# platine.net
KiCad netlist of a schematic drawn in EAGLE
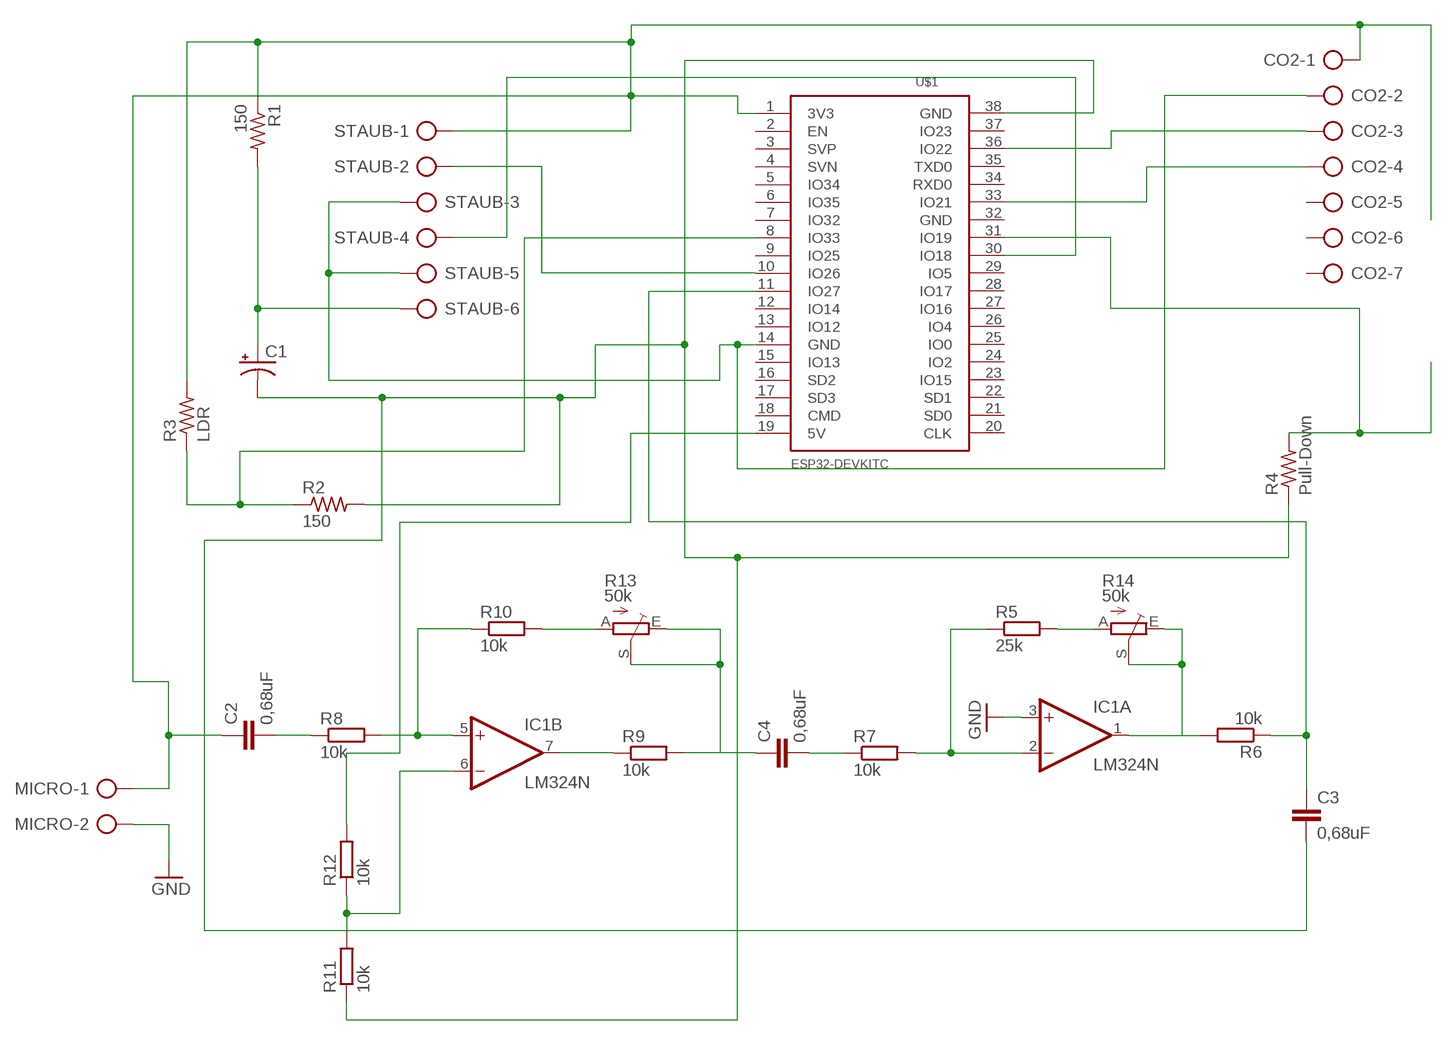
[diagram p0: schematic, sheet 1]

(export (version "E")
  (design (tool "Eeschema 10.0.6"))
  (components
    (comp (ref "C1")
      (value "CPOL-USE2,5-6E")
      (footprint "eagle-import:E2,5-6E")
      (libsource (lib "eagle-import") (part "CPOL-USE2,5-6E"))
    )
    (comp (ref "C2")
      (value "0,68uF")
      (footprint "eagle-import:C025-025X050")
      (libsource (lib "eagle-import") (part "C-EU025-025X050"))
    )
    (comp (ref "C3")
      (value "0,68uF")
      (footprint "eagle-import:C025-025X050")
      (libsource (lib "eagle-import") (part "C-EU025-025X050"))
    )
    (comp (ref "C4")
      (value "0,68uF")
      (footprint "eagle-import:C025-025X050")
      (libsource (lib "eagle-import") (part "C-EU025-025X050"))
    )
    (comp (ref "CO2")
      (value "AK300/7")
      (footprint "eagle-import:AK300_7")
      (libsource (lib "eagle-import") (part "AK300/7"))
    )
    (comp (ref "IC1")
      (value "LM324N")
      (footprint "eagle-import:DIL14")
      (libsource (lib "eagle-import") (part "LM324N"))
    )
    (comp (ref "MICRO")
      (value "AK300/2")
      (footprint "eagle-import:AK300_2")
      (libsource (lib "eagle-import") (part "AK300/2"))
    )
    (comp (ref "R1")
      (value "150")
      (footprint "eagle-import:0207_10")
      (libsource (lib "eagle-import") (part "R-US_0207/10"))
    )
    (comp (ref "R2")
      (value "150")
      (footprint "eagle-import:0207_10")
      (libsource (lib "eagle-import") (part "R-US_0207/10"))
    )
    (comp (ref "R3")
      (value "LDR")
      (footprint "eagle-import:V234_12")
      (libsource (lib "eagle-import") (part "R-US_V234/12"))
    )
    (comp (ref "R4")
      (value "Pull-Down")
      (footprint "eagle-import:0207_10")
      (libsource (lib "eagle-import") (part "R-US_0207/10"))
    )
    (comp (ref "R5")
      (value "25k")
      (footprint "eagle-import:0204_7")
      (libsource (lib "eagle-import") (part "R-EU_0204/7"))
    )
    (comp (ref "R6")
      (value "10k")
      (footprint "eagle-import:0204_7")
      (libsource (lib "eagle-import") (part "R-EU_0204/7"))
    )
    (comp (ref "R7")
      (value "10k")
      (footprint "eagle-import:0204_7")
      (libsource (lib "eagle-import") (part "R-EU_0204/7"))
    )
    (comp (ref "R8")
      (value "10k")
      (footprint "eagle-import:0204_7")
      (libsource (lib "eagle-import") (part "R-EU_0204/7"))
    )
    (comp (ref "R9")
      (value "10k")
      (footprint "eagle-import:0204_7")
      (libsource (lib "eagle-import") (part "R-EU_0204/7"))
    )
    (comp (ref "R10")
      (value "10k")
      (footprint "eagle-import:0204_7")
      (libsource (lib "eagle-import") (part "R-EU_0204/7"))
    )
    (comp (ref "R11")
      (value "10k")
      (footprint "eagle-import:0204_7")
      (libsource (lib "eagle-import") (part "R-EU_0204/7"))
    )
    (comp (ref "R12")
      (value "10k")
      (footprint "eagle-import:0204_7")
      (libsource (lib "eagle-import") (part "R-EU_0204/7"))
    )
    (comp (ref "R13")
      (value "50k")
      (footprint "eagle-import:LI10")
      (libsource (lib "eagle-import") (part "TRIM_EU-LI10"))
    )
    (comp (ref "R14")
      (value "50k")
      (footprint "eagle-import:LI10")
      (libsource (lib "eagle-import") (part "TRIM_EU-LI10"))
    )
    (comp (ref "STAUB")
      (value "AK300/6")
      (footprint "eagle-import:AK300_6")
      (libsource (lib "eagle-import") (part "AK300/6"))
    )
    (comp (ref "U$1")
      (value "ESP32DEVKITC")
      (footprint "eagle-import:ESP32-DEVKITC")
      (libsource (lib "eagle-import") (part "ESP32DEVKITC"))
    )
  )
  (nets
    (net (code "1") (name "GND") (class "Default")
      (node (ref "IC1") (pin "3") (pinfunction "+IN_3") (pintype "input"))
      (node (ref "MICRO") (pin "2") (pinfunction "KL_2") (pintype "passive"))
    )
    (net (code "2") (name "Net-(C1-Pad-)") (class "Default")
      (node (ref "C1") (pin "-") (pinfunction "-_-") (pintype "passive"))
      (node (ref "C3") (pin "2") (pinfunction "2_2") (pintype "passive"))
      (node (ref "R11") (pin "1") (pinfunction "1_1") (pintype "passive"))
      (node (ref "R2") (pin "2") (pinfunction "2_2") (pintype "passive"))
      (node (ref "R4") (pin "1") (pinfunction "1_1") (pintype "passive"))
      (node (ref "U$1") (pin "38") (pinfunction "GND_38") (pintype "bidirectional"))
    )
    (net (code "3") (name "Net-(C2-Pad2)") (class "Default")
      (node (ref "C2") (pin "2") (pinfunction "2_2") (pintype "passive"))
      (node (ref "R8") (pin "1") (pinfunction "1_1") (pintype "passive"))
    )
    (net (code "4") (name "Net-(C4-Pad1)") (class "Default")
      (node (ref "C4") (pin "1") (pinfunction "1_1") (pintype "passive"))
      (node (ref "R13") (pin "E") (pinfunction "E_E") (pintype "passive"))
      (node (ref "R13") (pin "S") (pinfunction "S_S") (pintype "passive"))
      (node (ref "R9") (pin "2") (pinfunction "2_2") (pintype "passive"))
    )
    (net (code "5") (name "Net-(C4-Pad2)") (class "Default")
      (node (ref "C4") (pin "2") (pinfunction "2_2") (pintype "passive"))
      (node (ref "R7") (pin "1") (pinfunction "1_1") (pintype "passive"))
    )
    (net (code "6") (name "Net-(CO2A-KL)") (class "Default")
      (node (ref "C2") (pin "1") (pinfunction "1_1") (pintype "passive"))
      (node (ref "CO2") (pin "1") (pinfunction "KL_1") (pintype "passive"))
      (node (ref "MICRO") (pin "1") (pinfunction "KL_1") (pintype "passive"))
      (node (ref "R1") (pin "1") (pinfunction "1_1") (pintype "passive"))
      (node (ref "R3") (pin "2") (pinfunction "2_2") (pintype "passive"))
      (node (ref "STAUB") (pin "1") (pinfunction "KL_1") (pintype "passive"))
      (node (ref "U$1") (pin "1") (pinfunction "3V3_1") (pintype "bidirectional"))
    )
    (net (code "7") (name "Net-(CO2B-KL)") (class "Default")
      (node (ref "CO2") (pin "2") (pinfunction "KL_2") (pintype "passive"))
      (node (ref "STAUB") (pin "3") (pinfunction "KL_3") (pintype "passive"))
      (node (ref "STAUB") (pin "5") (pinfunction "KL_5") (pintype "passive"))
      (node (ref "U$1") (pin "14") (pinfunction "GND_14") (pintype "bidirectional"))
    )
    (net (code "8") (name "Net-(CO2C-KL)") (class "Default")
      (node (ref "CO2") (pin "3") (pinfunction "KL_3") (pintype "passive"))
      (node (ref "U$1") (pin "36") (pinfunction "IO22_36") (pintype "bidirectional"))
    )
    (net (code "9") (name "Net-(CO2D-KL)") (class "Default")
      (node (ref "CO2") (pin "4") (pinfunction "KL_4") (pintype "passive"))
      (node (ref "U$1") (pin "33") (pinfunction "IO21_33") (pintype "bidirectional"))
    )
    (net (code "10") (name "Net-(IC1A--IN)") (class "Default")
      (node (ref "IC1") (pin "2") (pinfunction "-IN_2") (pintype "input"))
      (node (ref "R5") (pin "1") (pinfunction "1_1") (pintype "passive"))
      (node (ref "R7") (pin "2") (pinfunction "2_2") (pintype "passive"))
    )
    (net (code "11") (name "Net-(IC1A-OUT)") (class "Default")
      (node (ref "IC1") (pin "1") (pinfunction "OUT_1") (pintype "output"))
      (node (ref "R14") (pin "E") (pinfunction "E_E") (pintype "passive"))
      (node (ref "R14") (pin "S") (pinfunction "S_S") (pintype "passive"))
      (node (ref "R6") (pin "2") (pinfunction "2_2") (pintype "passive"))
    )
    (net (code "12") (name "Net-(IC1B-+IN)") (class "Default")
      (node (ref "IC1") (pin "5") (pinfunction "+IN_5") (pintype "input"))
      (node (ref "R10") (pin "1") (pinfunction "1_1") (pintype "passive"))
      (node (ref "R8") (pin "2") (pinfunction "2_2") (pintype "passive"))
    )
    (net (code "13") (name "Net-(IC1B--IN)") (class "Default")
      (node (ref "IC1") (pin "6") (pinfunction "-IN_6") (pintype "input"))
      (node (ref "R11") (pin "2") (pinfunction "2_2") (pintype "passive"))
      (node (ref "R12") (pin "1") (pinfunction "1_1") (pintype "passive"))
    )
    (net (code "14") (name "Net-(IC1B-OUT)") (class "Default")
      (node (ref "IC1") (pin "7") (pinfunction "OUT_7") (pintype "output"))
      (node (ref "R9") (pin "1") (pinfunction "1_1") (pintype "passive"))
    )
    (net (code "15") (name "Net-(R10-Pad2)") (class "Default")
      (node (ref "R10") (pin "2") (pinfunction "2_2") (pintype "passive"))
      (node (ref "R13") (pin "A") (pinfunction "A_A") (pintype "passive"))
    )
    (net (code "16") (name "Net-(R14-PadA)") (class "Default")
      (node (ref "R14") (pin "A") (pinfunction "A_A") (pintype "passive"))
      (node (ref "R5") (pin "2") (pinfunction "2_2") (pintype "passive"))
    )
    (net (code "17") (name "Net-(STAUBB-KL)") (class "Default")
      (node (ref "STAUB") (pin "2") (pinfunction "KL_2") (pintype "passive"))
      (node (ref "U$1") (pin "10") (pinfunction "IO26_10") (pintype "bidirectional"))
    )
    (net (code "18") (name "Net-(STAUBD-KL)") (class "Default")
      (node (ref "STAUB") (pin "4") (pinfunction "KL_4") (pintype "passive"))
      (node (ref "U$1") (pin "30") (pinfunction "IO18_30") (pintype "bidirectional"))
    )
    (net (code "19") (name "Net-(STAUBF-KL)") (class "Default")
      (node (ref "C1") (pin "+") (pinfunction "+_+") (pintype "passive"))
      (node (ref "R1") (pin "2") (pinfunction "2_2") (pintype "passive"))
      (node (ref "STAUB") (pin "6") (pinfunction "KL_6") (pintype "passive"))
    )
    (net (code "20") (name "Net-(U$1-5V)") (class "Default")
      (node (ref "R12") (pin "2") (pinfunction "2_2") (pintype "passive"))
      (node (ref "U$1") (pin "19") (pinfunction "5V_19") (pintype "bidirectional"))
    )
    (net (code "21") (name "Net-(U$1-IO19)") (class "Default")
      (node (ref "R4") (pin "2") (pinfunction "2_2") (pintype "passive"))
      (node (ref "U$1") (pin "31") (pinfunction "IO19_31") (pintype "bidirectional"))
    )
    (net (code "22") (name "Net-(U$1-IO27)") (class "Default")
      (node (ref "C3") (pin "1") (pinfunction "1_1") (pintype "passive"))
      (node (ref "R6") (pin "1") (pinfunction "1_1") (pintype "passive"))
      (node (ref "U$1") (pin "11") (pinfunction "IO27_11") (pintype "bidirectional"))
    )
    (net (code "23") (name "Net-(U$1-IO33)") (class "Default")
      (node (ref "R2") (pin "1") (pinfunction "1_1") (pintype "passive"))
      (node (ref "R3") (pin "1") (pinfunction "1_1") (pintype "passive"))
      (node (ref "U$1") (pin "8") (pinfunction "IO33_8") (pintype "bidirectional"))
    )
    (net (code "24") (name "unconnected-(CO2E-KL-Pad5)") (class "Default")
      (node (ref "CO2") (pin "5") (pinfunction "KL_5") (pintype "passive"))
    )
    (net (code "25") (name "unconnected-(CO2F-KL-Pad6)") (class "Default")
      (node (ref "CO2") (pin "6") (pinfunction "KL_6") (pintype "passive"))
    )
    (net (code "26") (name "unconnected-(CO2G-KL-Pad7)") (class "Default")
      (node (ref "CO2") (pin "7") (pinfunction "KL_7") (pintype "passive"))
    )
    (net (code "27") (name "unconnected-(U$1-CLK-Pad20)") (class "Default")
      (node (ref "U$1") (pin "20") (pinfunction "CLK_20") (pintype "bidirectional"))
    )
    (net (code "28") (name "unconnected-(U$1-CMD-Pad18)") (class "Default")
      (node (ref "U$1") (pin "18") (pinfunction "CMD_18") (pintype "bidirectional"))
    )
    (net (code "29") (name "unconnected-(U$1-EN-Pad2)") (class "Default")
      (node (ref "U$1") (pin "2") (pinfunction "EN_2") (pintype "bidirectional"))
    )
    (net (code "30") (name "unconnected-(U$1-GND-Pad32)") (class "Default")
      (node (ref "U$1") (pin "32") (pinfunction "GND_32") (pintype "bidirectional"))
    )
    (net (code "31") (name "unconnected-(U$1-IO0-Pad25)") (class "Default")
      (node (ref "U$1") (pin "25") (pinfunction "IO0_25") (pintype "bidirectional"))
    )
    (net (code "32") (name "unconnected-(U$1-IO2-Pad24)") (class "Default")
      (node (ref "U$1") (pin "24") (pinfunction "IO2_24") (pintype "bidirectional"))
    )
    (net (code "33") (name "unconnected-(U$1-IO4-Pad26)") (class "Default")
      (node (ref "U$1") (pin "26") (pinfunction "IO4_26") (pintype "bidirectional"))
    )
    (net (code "34") (name "unconnected-(U$1-IO5-Pad29)") (class "Default")
      (node (ref "U$1") (pin "29") (pinfunction "IO5_29") (pintype "bidirectional"))
    )
    (net (code "35") (name "unconnected-(U$1-IO12-Pad13)") (class "Default")
      (node (ref "U$1") (pin "13") (pinfunction "IO12_13") (pintype "bidirectional"))
    )
    (net (code "36") (name "unconnected-(U$1-IO13-Pad15)") (class "Default")
      (node (ref "U$1") (pin "15") (pinfunction "IO13_15") (pintype "bidirectional"))
    )
    (net (code "37") (name "unconnected-(U$1-IO14-Pad12)") (class "Default")
      (node (ref "U$1") (pin "12") (pinfunction "IO14_12") (pintype "bidirectional"))
    )
    (net (code "38") (name "unconnected-(U$1-IO15-Pad23)") (class "Default")
      (node (ref "U$1") (pin "23") (pinfunction "IO15_23") (pintype "bidirectional"))
    )
    (net (code "39") (name "unconnected-(U$1-IO16-Pad27)") (class "Default")
      (node (ref "U$1") (pin "27") (pinfunction "IO16_27") (pintype "bidirectional"))
    )
    (net (code "40") (name "unconnected-(U$1-IO17-Pad28)") (class "Default")
      (node (ref "U$1") (pin "28") (pinfunction "IO17_28") (pintype "bidirectional"))
    )
    (net (code "41") (name "unconnected-(U$1-IO23-Pad37)") (class "Default")
      (node (ref "U$1") (pin "37") (pinfunction "IO23_37") (pintype "bidirectional"))
    )
    (net (code "42") (name "unconnected-(U$1-IO25-Pad9)") (class "Default")
      (node (ref "U$1") (pin "9") (pinfunction "IO25_9") (pintype "bidirectional"))
    )
    (net (code "43") (name "unconnected-(U$1-IO32-Pad7)") (class "Default")
      (node (ref "U$1") (pin "7") (pinfunction "IO32_7") (pintype "bidirectional"))
    )
    (net (code "44") (name "unconnected-(U$1-IO34-Pad5)") (class "Default")
      (node (ref "U$1") (pin "5") (pinfunction "IO34_5") (pintype "bidirectional"))
    )
    (net (code "45") (name "unconnected-(U$1-IO35-Pad6)") (class "Default")
      (node (ref "U$1") (pin "6") (pinfunction "IO35_6") (pintype "bidirectional"))
    )
    (net (code "46") (name "unconnected-(U$1-RXD0-Pad34)") (class "Default")
      (node (ref "U$1") (pin "34") (pinfunction "RXD0_34") (pintype "bidirectional"))
    )
    (net (code "47") (name "unconnected-(U$1-SD0-Pad21)") (class "Default")
      (node (ref "U$1") (pin "21") (pinfunction "SD0_21") (pintype "bidirectional"))
    )
    (net (code "48") (name "unconnected-(U$1-SD1-Pad22)") (class "Default")
      (node (ref "U$1") (pin "22") (pinfunction "SD1_22") (pintype "bidirectional"))
    )
    (net (code "49") (name "unconnected-(U$1-SD2-Pad16)") (class "Default")
      (node (ref "U$1") (pin "16") (pinfunction "SD2_16") (pintype "bidirectional"))
    )
    (net (code "50") (name "unconnected-(U$1-SD3-Pad17)") (class "Default")
      (node (ref "U$1") (pin "17") (pinfunction "SD3_17") (pintype "bidirectional"))
    )
    (net (code "51") (name "unconnected-(U$1-SVN-Pad4)") (class "Default")
      (node (ref "U$1") (pin "4") (pinfunction "SVN_4") (pintype "bidirectional"))
    )
    (net (code "52") (name "unconnected-(U$1-SVP-Pad3)") (class "Default")
      (node (ref "U$1") (pin "3") (pinfunction "SVP_3") (pintype "bidirectional"))
    )
    (net (code "53") (name "unconnected-(U$1-TXD0-Pad35)") (class "Default")
      (node (ref "U$1") (pin "35") (pinfunction "TXD0_35") (pintype "bidirectional"))
    )
  )
)
